# MODULE_STRAPS_MD.net
KiCad netlist of a schematic drawn in Altium Designer
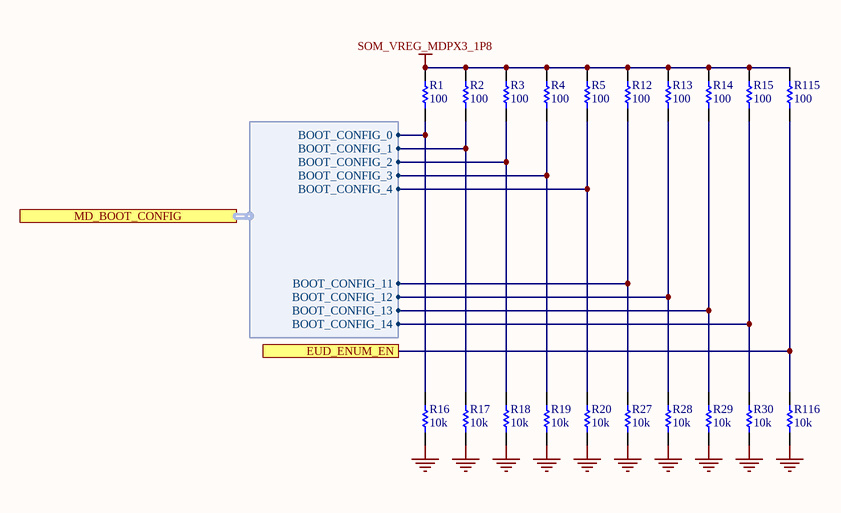
[diagram p0: MODULE_STRAPS_MD.SchDoc]

(export (version "E")
  (design (tool "Eeschema 10.0.6"))
  (components
    (comp (ref "R1")
      (value "100")
      (footprint "RES-0201")
      (description "RES CHIP 0201 100R 1% 1/20W")
      (fields (field (name "POWER") "50mW") (field (name "TOLERANCE") "1%"))
      (libsource (lib "Clean") (part "RES"))
    )
    (comp (ref "R2")
      (value "100")
      (footprint "RES-0201")
      (description "RES CHIP 0201 100R 1% 1/20W")
      (fields (field (name "POWER") "50mW") (field (name "TOLERANCE") "1%"))
      (libsource (lib "Clean") (part "RES"))
    )
    (comp (ref "R3")
      (value "100")
      (footprint "RES-0201")
      (description "RES CHIP 0201 100R 1% 1/20W")
      (fields (field (name "POWER") "50mW") (field (name "TOLERANCE") "1%"))
      (libsource (lib "Clean") (part "RES"))
    )
    (comp (ref "R4")
      (value "100")
      (footprint "RES-0201")
      (description "RES CHIP 0201 100R 1% 1/20W")
      (fields (field (name "POWER") "50mW") (field (name "TOLERANCE") "1%"))
      (libsource (lib "Clean") (part "RES"))
    )
    (comp (ref "R5")
      (value "100")
      (footprint "RES-0201")
      (description "RES CHIP 0201 100R 1% 1/20W")
      (fields (field (name "POWER") "50mW") (field (name "TOLERANCE") "1%"))
      (libsource (lib "Clean") (part "RES"))
    )
    (comp (ref "R12")
      (value "100")
      (footprint "RES-0201")
      (description "RES CHIP 0201 100R 1% 1/20W")
      (fields (field (name "POWER") "50mW") (field (name "TOLERANCE") "1%"))
      (libsource (lib "Clean") (part "RES"))
    )
    (comp (ref "R13")
      (value "100")
      (footprint "RES-0201")
      (description "RES CHIP 0201 100R 1% 1/20W")
      (fields (field (name "POWER") "50mW") (field (name "TOLERANCE") "1%"))
      (libsource (lib "Clean") (part "RES"))
    )
    (comp (ref "R14")
      (value "100")
      (footprint "RES-0201")
      (description "RES CHIP 0201 100R 1% 1/20W")
      (fields (field (name "POWER") "50mW") (field (name "TOLERANCE") "1%"))
      (libsource (lib "Clean") (part "RES"))
    )
    (comp (ref "R15")
      (value "100")
      (footprint "RES-0201")
      (description "RES CHIP 0201 100R 1% 1/20W")
      (fields (field (name "POWER") "50mW") (field (name "TOLERANCE") "1%"))
      (libsource (lib "Clean") (part "RES"))
    )
    (comp (ref "R16")
      (value "10k")
      (footprint "RES-0201")
      (description "RES CHIP 0201 10k 1% 1/20W")
      (fields (field (name "POWER") "50mW") (field (name "TOLERANCE") "1%"))
      (libsource (lib "Clean") (part "RES"))
    )
    (comp (ref "R17")
      (value "10k")
      (footprint "RES-0201")
      (description "RES CHIP 0201 10k 1% 1/20W")
      (fields (field (name "POWER") "50mW") (field (name "TOLERANCE") "1%"))
      (libsource (lib "Clean") (part "RES"))
    )
    (comp (ref "R18")
      (value "10k")
      (footprint "RES-0201")
      (description "RES CHIP 0201 10k 1% 1/20W")
      (fields (field (name "POWER") "50mW") (field (name "TOLERANCE") "1%"))
      (libsource (lib "Clean") (part "RES"))
    )
    (comp (ref "R19")
      (value "10k")
      (footprint "RES-0201")
      (description "RES CHIP 0201 10k 1% 1/20W")
      (fields (field (name "POWER") "50mW") (field (name "TOLERANCE") "1%"))
      (libsource (lib "Clean") (part "RES"))
    )
    (comp (ref "R20")
      (value "10k")
      (footprint "RES-0201")
      (description "RES CHIP 0201 10k 1% 1/20W")
      (fields (field (name "POWER") "50mW") (field (name "TOLERANCE") "1%"))
      (libsource (lib "Clean") (part "RES"))
    )
    (comp (ref "R27")
      (value "10k")
      (footprint "RES-0201")
      (description "RES CHIP 0201 10k 1% 1/20W")
      (fields (field (name "POWER") "50mW") (field (name "TOLERANCE") "1%"))
      (libsource (lib "Clean") (part "RES"))
    )
    (comp (ref "R28")
      (value "10k")
      (footprint "RES-0201")
      (description "RES CHIP 0201 10k 1% 1/20W")
      (fields (field (name "POWER") "50mW") (field (name "TOLERANCE") "1%"))
      (libsource (lib "Clean") (part "RES"))
    )
    (comp (ref "R29")
      (value "10k")
      (footprint "RES-0201")
      (description "RES CHIP 0201 10k 1% 1/20W")
      (fields (field (name "POWER") "50mW") (field (name "TOLERANCE") "1%"))
      (libsource (lib "Clean") (part "RES"))
    )
    (comp (ref "R30")
      (value "10k")
      (footprint "RES-0201")
      (description "RES CHIP 0201 10k 1% 1/20W")
      (fields (field (name "POWER") "50mW") (field (name "TOLERANCE") "1%"))
      (libsource (lib "Clean") (part "RES"))
    )
    (comp (ref "R115")
      (value "100")
      (footprint "RES-0201")
      (description "RES CHIP 0201 100R 1% 1/20W")
      (fields (field (name "POWER") "50mW") (field (name "TOLERANCE") "1%"))
      (libsource (lib "Clean") (part "RES"))
    )
    (comp (ref "R116")
      (value "10k")
      (footprint "RES-0201")
      (description "RES CHIP 0201 10k 1% 1/20W")
      (fields (field (name "POWER") "50mW") (field (name "TOLERANCE") "1%"))
      (libsource (lib "Clean") (part "RES"))
    )
  )
  (nets
    (net (code "2") (name "/EUD_ENUM_EN") (class "Default")
      (node (ref "R115") (pin "2") (pinfunction "2_2") (pintype "passive"))
      (node (ref "R116") (pin "2") (pinfunction "2_2") (pintype "passive"))
    )
    (net (code "4") (name "GND") (class "Default")
      (node (ref "R116") (pin "1") (pinfunction "1_1") (pintype "passive"))
      (node (ref "R16") (pin "1") (pinfunction "1_1") (pintype "passive"))
      (node (ref "R17") (pin "1") (pinfunction "1_1") (pintype "passive"))
      (node (ref "R18") (pin "1") (pinfunction "1_1") (pintype "passive"))
      (node (ref "R19") (pin "1") (pinfunction "1_1") (pintype "passive"))
      (node (ref "R20") (pin "1") (pinfunction "1_1") (pintype "passive"))
      (node (ref "R27") (pin "1") (pinfunction "1_1") (pintype "passive"))
      (node (ref "R28") (pin "1") (pinfunction "1_1") (pintype "passive"))
      (node (ref "R29") (pin "1") (pinfunction "1_1") (pintype "passive"))
      (node (ref "R30") (pin "1") (pinfunction "1_1") (pintype "passive"))
    )
    (net (code "5") (name "Net-(R1-Pad2)") (class "Default")
      (node (ref "R1") (pin "2") (pinfunction "2_2") (pintype "passive"))
      (node (ref "R16") (pin "2") (pinfunction "2_2") (pintype "passive"))
    )
    (net (code "6") (name "Net-(R12-Pad2)") (class "Default")
      (node (ref "R12") (pin "2") (pinfunction "2_2") (pintype "passive"))
      (node (ref "R27") (pin "2") (pinfunction "2_2") (pintype "passive"))
    )
    (net (code "7") (name "Net-(R13-Pad2)") (class "Default")
      (node (ref "R13") (pin "2") (pinfunction "2_2") (pintype "passive"))
      (node (ref "R28") (pin "2") (pinfunction "2_2") (pintype "passive"))
    )
    (net (code "8") (name "Net-(R14-Pad2)") (class "Default")
      (node (ref "R14") (pin "2") (pinfunction "2_2") (pintype "passive"))
      (node (ref "R29") (pin "2") (pinfunction "2_2") (pintype "passive"))
    )
    (net (code "9") (name "Net-(R15-Pad2)") (class "Default")
      (node (ref "R15") (pin "2") (pinfunction "2_2") (pintype "passive"))
      (node (ref "R30") (pin "2") (pinfunction "2_2") (pintype "passive"))
    )
    (net (code "10") (name "Net-(R17-Pad2)") (class "Default")
      (node (ref "R17") (pin "2") (pinfunction "2_2") (pintype "passive"))
      (node (ref "R2") (pin "2") (pinfunction "2_2") (pintype "passive"))
    )
    (net (code "11") (name "Net-(R18-Pad2)") (class "Default")
      (node (ref "R18") (pin "2") (pinfunction "2_2") (pintype "passive"))
      (node (ref "R3") (pin "2") (pinfunction "2_2") (pintype "passive"))
    )
    (net (code "12") (name "Net-(R19-Pad2)") (class "Default")
      (node (ref "R19") (pin "2") (pinfunction "2_2") (pintype "passive"))
      (node (ref "R4") (pin "2") (pinfunction "2_2") (pintype "passive"))
    )
    (net (code "13") (name "Net-(R20-Pad2)") (class "Default")
      (node (ref "R20") (pin "2") (pinfunction "2_2") (pintype "passive"))
      (node (ref "R5") (pin "2") (pinfunction "2_2") (pintype "passive"))
    )
    (net (code "14") (name "SOM_VREG_MDPX3_1P8") (class "Default")
      (node (ref "R1") (pin "1") (pinfunction "1_1") (pintype "passive"))
      (node (ref "R115") (pin "1") (pinfunction "1_1") (pintype "passive"))
      (node (ref "R12") (pin "1") (pinfunction "1_1") (pintype "passive"))
      (node (ref "R13") (pin "1") (pinfunction "1_1") (pintype "passive"))
      (node (ref "R14") (pin "1") (pinfunction "1_1") (pintype "passive"))
      (node (ref "R15") (pin "1") (pinfunction "1_1") (pintype "passive"))
      (node (ref "R2") (pin "1") (pinfunction "1_1") (pintype "passive"))
      (node (ref "R3") (pin "1") (pinfunction "1_1") (pintype "passive"))
      (node (ref "R4") (pin "1") (pinfunction "1_1") (pintype "passive"))
      (node (ref "R5") (pin "1") (pinfunction "1_1") (pintype "passive"))
    )
  )
)
